# Digital_Port_C_State_LED_Inducator.net
KiCad netlist of a schematic drawn in Altium Designer
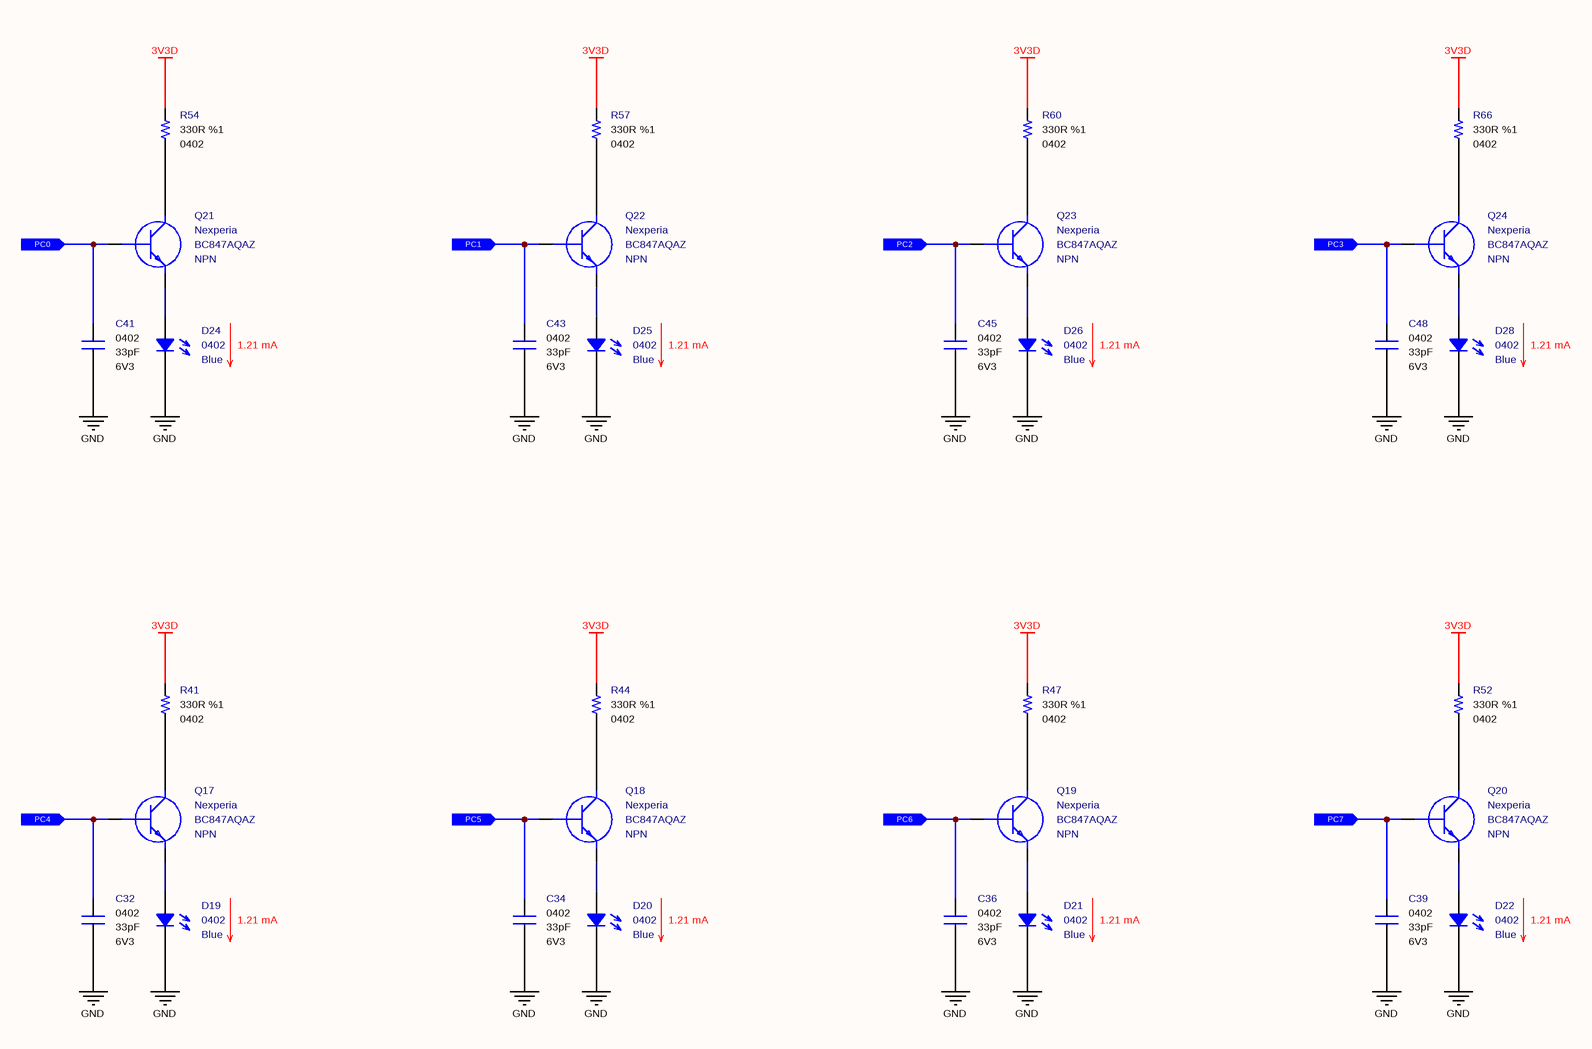
[diagram p0: Digital Port C State LED Inducator.SchDoc]

(export (version "E")
  (design (tool "Eeschema 10.0.6"))
  (components
    (comp (ref "C32")
      (value "33pF")
      (footprint "CAPACITOR_0402")
      (description "Capacitor - 33pF [0402] (Ceramic)")
      (fields
        (field (name "CASE") "0402")
        (field (name "TOLERANCE") "10%")
        (field (name "VOLTAGE") "6V3")
        (field (name "MANUFACTURER PART NUMBER") "C0402C330J9RACAUTO")
      )
      (libsource (lib "Ovoo_Library") (part "Capacitor - 33pF [0402-6V3]"))
    )
    (comp (ref "C34")
      (value "33pF")
      (footprint "CAPACITOR_0402")
      (description "Capacitor - 33pF [0402] (Ceramic)")
      (fields
        (field (name "CASE") "0402")
        (field (name "TOLERANCE") "10%")
        (field (name "VOLTAGE") "6V3")
        (field (name "MANUFACTURER PART NUMBER") "C0402C330J9RACAUTO")
      )
      (libsource (lib "Ovoo_Library") (part "Capacitor - 33pF [0402-6V3]"))
    )
    (comp (ref "C36")
      (value "33pF")
      (footprint "CAPACITOR_0402")
      (description "Capacitor - 33pF [0402] (Ceramic)")
      (fields
        (field (name "CASE") "0402")
        (field (name "TOLERANCE") "10%")
        (field (name "VOLTAGE") "6V3")
        (field (name "MANUFACTURER PART NUMBER") "C0402C330J9RACAUTO")
      )
      (libsource (lib "Ovoo_Library") (part "Capacitor - 33pF [0402-6V3]"))
    )
    (comp (ref "C39")
      (value "33pF")
      (footprint "CAPACITOR_0402")
      (description "Capacitor - 33pF [0402] (Ceramic)")
      (fields
        (field (name "CASE") "0402")
        (field (name "TOLERANCE") "10%")
        (field (name "VOLTAGE") "6V3")
        (field (name "MANUFACTURER PART NUMBER") "C0402C330J9RACAUTO")
      )
      (libsource (lib "Ovoo_Library") (part "Capacitor - 33pF [0402-6V3]"))
    )
    (comp (ref "C41")
      (value "33pF")
      (footprint "CAPACITOR_0402")
      (description "Capacitor - 33pF [0402] (Ceramic)")
      (fields
        (field (name "CASE") "0402")
        (field (name "TOLERANCE") "10%")
        (field (name "VOLTAGE") "6V3")
        (field (name "MANUFACTURER PART NUMBER") "C0402C330J9RACAUTO")
      )
      (libsource (lib "Ovoo_Library") (part "Capacitor - 33pF [0402-6V3]"))
    )
    (comp (ref "C43")
      (value "33pF")
      (footprint "CAPACITOR_0402")
      (description "Capacitor - 33pF [0402] (Ceramic)")
      (fields
        (field (name "CASE") "0402")
        (field (name "TOLERANCE") "10%")
        (field (name "VOLTAGE") "6V3")
        (field (name "MANUFACTURER PART NUMBER") "C0402C330J9RACAUTO")
      )
      (libsource (lib "Ovoo_Library") (part "Capacitor - 33pF [0402-6V3]"))
    )
    (comp (ref "C45")
      (value "33pF")
      (footprint "CAPACITOR_0402")
      (description "Capacitor - 33pF [0402] (Ceramic)")
      (fields
        (field (name "CASE") "0402")
        (field (name "TOLERANCE") "10%")
        (field (name "VOLTAGE") "6V3")
        (field (name "MANUFACTURER PART NUMBER") "C0402C330J9RACAUTO")
      )
      (libsource (lib "Ovoo_Library") (part "Capacitor - 33pF [0402-6V3]"))
    )
    (comp (ref "C48")
      (value "33pF")
      (footprint "CAPACITOR_0402")
      (description "Capacitor - 33pF [0402] (Ceramic)")
      (fields
        (field (name "CASE") "0402")
        (field (name "TOLERANCE") "10%")
        (field (name "VOLTAGE") "6V3")
        (field (name "MANUFACTURER PART NUMBER") "C0402C330J9RACAUTO")
      )
      (libsource (lib "Ovoo_Library") (part "Capacitor - 33pF [0402-6V3]"))
    )
    (comp (ref "D19")
      (value "SMD LED (Blue)")
      (footprint "LED_0402")
      (description "Standard LEDs - SMD PICOLEDTM;BLUE LED; 25M @ 5MA")
      (fields
        (field (name "MANUFACTURER_PART_NUMBER") "SMLP13BC8TT86")
        (field (name "MOUSER_PART_NUMBER") "755-SMLP13BC8TT86")
        (field (name "CASE") "0402")
        (field (name "COLOR") "Blue")
      )
      (libsource (lib "Ovoo_Library") (part "Diode - LED (0402-Blue)"))
    )
    (comp (ref "D20")
      (value "SMD LED (Blue)")
      (footprint "LED_0402")
      (description "Standard LEDs - SMD PICOLEDTM;BLUE LED; 25M @ 5MA")
      (fields
        (field (name "MANUFACTURER_PART_NUMBER") "SMLP13BC8TT86")
        (field (name "MOUSER_PART_NUMBER") "755-SMLP13BC8TT86")
        (field (name "CASE") "0402")
        (field (name "COLOR") "Blue")
      )
      (libsource (lib "Ovoo_Library") (part "Diode - LED (0402-Blue)"))
    )
    (comp (ref "D21")
      (value "SMD LED (Blue)")
      (footprint "LED_0402")
      (description "Standard LEDs - SMD PICOLEDTM;BLUE LED; 25M @ 5MA")
      (fields
        (field (name "MANUFACTURER_PART_NUMBER") "SMLP13BC8TT86")
        (field (name "MOUSER_PART_NUMBER") "755-SMLP13BC8TT86")
        (field (name "CASE") "0402")
        (field (name "COLOR") "Blue")
      )
      (libsource (lib "Ovoo_Library") (part "Diode - LED (0402-Blue)"))
    )
    (comp (ref "D22")
      (value "SMD LED (Blue)")
      (footprint "LED_0402")
      (description "Standard LEDs - SMD PICOLEDTM;BLUE LED; 25M @ 5MA")
      (fields
        (field (name "MANUFACTURER_PART_NUMBER") "SMLP13BC8TT86")
        (field (name "MOUSER_PART_NUMBER") "755-SMLP13BC8TT86")
        (field (name "CASE") "0402")
        (field (name "COLOR") "Blue")
      )
      (libsource (lib "Ovoo_Library") (part "Diode - LED (0402-Blue)"))
    )
    (comp (ref "D24")
      (value "SMD LED (Blue)")
      (footprint "LED_0402")
      (description "Standard LEDs - SMD PICOLEDTM;BLUE LED; 25M @ 5MA")
      (fields
        (field (name "MANUFACTURER_PART_NUMBER") "SMLP13BC8TT86")
        (field (name "MOUSER_PART_NUMBER") "755-SMLP13BC8TT86")
        (field (name "CASE") "0402")
        (field (name "COLOR") "Blue")
      )
      (libsource (lib "Ovoo_Library") (part "Diode - LED (0402-Blue)"))
    )
    (comp (ref "D25")
      (value "SMD LED (Blue)")
      (footprint "LED_0402")
      (description "Standard LEDs - SMD PICOLEDTM;BLUE LED; 25M @ 5MA")
      (fields
        (field (name "MANUFACTURER_PART_NUMBER") "SMLP13BC8TT86")
        (field (name "MOUSER_PART_NUMBER") "755-SMLP13BC8TT86")
        (field (name "CASE") "0402")
        (field (name "COLOR") "Blue")
      )
      (libsource (lib "Ovoo_Library") (part "Diode - LED (0402-Blue)"))
    )
    (comp (ref "D26")
      (value "SMD LED (Blue)")
      (footprint "LED_0402")
      (description "Standard LEDs - SMD PICOLEDTM;BLUE LED; 25M @ 5MA")
      (fields
        (field (name "MANUFACTURER_PART_NUMBER") "SMLP13BC8TT86")
        (field (name "MOUSER_PART_NUMBER") "755-SMLP13BC8TT86")
        (field (name "CASE") "0402")
        (field (name "COLOR") "Blue")
      )
      (libsource (lib "Ovoo_Library") (part "Diode - LED (0402-Blue)"))
    )
    (comp (ref "D28")
      (value "SMD LED (Blue)")
      (footprint "LED_0402")
      (description "Standard LEDs - SMD PICOLEDTM;BLUE LED; 25M @ 5MA")
      (fields
        (field (name "MANUFACTURER_PART_NUMBER") "SMLP13BC8TT86")
        (field (name "MOUSER_PART_NUMBER") "755-SMLP13BC8TT86")
        (field (name "CASE") "0402")
        (field (name "COLOR") "Blue")
      )
      (libsource (lib "Ovoo_Library") (part "Diode - LED (0402-Blue)"))
    )
    (comp (ref "Q17")
      (value "Bipolar NPN Transistors")
      (footprint "SOT1215")
      (description "Bipolar Transistors - BJT BC847AQA/DFN1010D-3/REEL 7\" Q2")
      (fields
        (field (name "MOUSER_PART_NUMBER") "771-BC847AQAZ")
        (field (name "MANUFACTURER_NAME") "Nexperia")
        (field (name "MANUFACTURER_PART_NUMBER") "BC847AQAZ")
        (field (name "POLARITY") "NPN")
      )
      (libsource (lib "Ovoo_Library") (part "Transistor - BC847"))
    )
    (comp (ref "Q18")
      (value "Bipolar NPN Transistors")
      (footprint "SOT1215")
      (description "Bipolar Transistors - BJT BC847AQA/DFN1010D-3/REEL 7\" Q2")
      (fields
        (field (name "MOUSER_PART_NUMBER") "771-BC847AQAZ")
        (field (name "MANUFACTURER_NAME") "Nexperia")
        (field (name "MANUFACTURER_PART_NUMBER") "BC847AQAZ")
        (field (name "POLARITY") "NPN")
      )
      (libsource (lib "Ovoo_Library") (part "Transistor - BC847"))
    )
    (comp (ref "Q19")
      (value "Bipolar NPN Transistors")
      (footprint "SOT1215")
      (description "Bipolar Transistors - BJT BC847AQA/DFN1010D-3/REEL 7\" Q2")
      (fields
        (field (name "MOUSER_PART_NUMBER") "771-BC847AQAZ")
        (field (name "MANUFACTURER_NAME") "Nexperia")
        (field (name "MANUFACTURER_PART_NUMBER") "BC847AQAZ")
        (field (name "POLARITY") "NPN")
      )
      (libsource (lib "Ovoo_Library") (part "Transistor - BC847"))
    )
    (comp (ref "Q20")
      (value "Bipolar NPN Transistors")
      (footprint "SOT1215")
      (description "Bipolar Transistors - BJT BC847AQA/DFN1010D-3/REEL 7\" Q2")
      (fields
        (field (name "MOUSER_PART_NUMBER") "771-BC847AQAZ")
        (field (name "MANUFACTURER_NAME") "Nexperia")
        (field (name "MANUFACTURER_PART_NUMBER") "BC847AQAZ")
        (field (name "POLARITY") "NPN")
      )
      (libsource (lib "Ovoo_Library") (part "Transistor - BC847"))
    )
    (comp (ref "Q21")
      (value "Bipolar NPN Transistors")
      (footprint "SOT1215")
      (description "Bipolar Transistors - BJT BC847AQA/DFN1010D-3/REEL 7\" Q2")
      (fields
        (field (name "MOUSER_PART_NUMBER") "771-BC847AQAZ")
        (field (name "MANUFACTURER_NAME") "Nexperia")
        (field (name "MANUFACTURER_PART_NUMBER") "BC847AQAZ")
        (field (name "POLARITY") "NPN")
      )
      (libsource (lib "Ovoo_Library") (part "Transistor - BC847"))
    )
    (comp (ref "Q22")
      (value "Bipolar NPN Transistors")
      (footprint "SOT1215")
      (description "Bipolar Transistors - BJT BC847AQA/DFN1010D-3/REEL 7\" Q2")
      (fields
        (field (name "MOUSER_PART_NUMBER") "771-BC847AQAZ")
        (field (name "MANUFACTURER_NAME") "Nexperia")
        (field (name "MANUFACTURER_PART_NUMBER") "BC847AQAZ")
        (field (name "POLARITY") "NPN")
      )
      (libsource (lib "Ovoo_Library") (part "Transistor - BC847"))
    )
    (comp (ref "Q23")
      (value "Bipolar NPN Transistors")
      (footprint "SOT1215")
      (description "Bipolar Transistors - BJT BC847AQA/DFN1010D-3/REEL 7\" Q2")
      (fields
        (field (name "MOUSER_PART_NUMBER") "771-BC847AQAZ")
        (field (name "MANUFACTURER_NAME") "Nexperia")
        (field (name "MANUFACTURER_PART_NUMBER") "BC847AQAZ")
        (field (name "POLARITY") "NPN")
      )
      (libsource (lib "Ovoo_Library") (part "Transistor - BC847"))
    )
    (comp (ref "Q24")
      (value "Bipolar NPN Transistors")
      (footprint "SOT1215")
      (description "Bipolar Transistors - BJT BC847AQA/DFN1010D-3/REEL 7\" Q2")
      (fields
        (field (name "MOUSER_PART_NUMBER") "771-BC847AQAZ")
        (field (name "MANUFACTURER_NAME") "Nexperia")
        (field (name "MANUFACTURER_PART_NUMBER") "BC847AQAZ")
        (field (name "POLARITY") "NPN")
      )
      (libsource (lib "Ovoo_Library") (part "Transistor - BC847"))
    )
    (comp (ref "R41")
      (value "330R")
      (footprint "RESISTOR_0402")
      (description "Thick Film Resistors - SMD 1/16 W 330 Ohm 1%")
      (fields
        (field (name "TOLERANCE") "%1")
        (field (name "CASE") "0402")
        (field (name "MANUFACTURER PART NUMBER") "CRCW0402330RFKED")
        (field (name "MOUSER PART NUMBER") "71-CRCW0402-330-E3")
      )
      (libsource (lib "Ovoo_Library") (part "Resistor - 330R"))
    )
    (comp (ref "R44")
      (value "330R")
      (footprint "RESISTOR_0402")
      (description "Thick Film Resistors - SMD 1/16 W 330 Ohm 1%")
      (fields
        (field (name "TOLERANCE") "%1")
        (field (name "CASE") "0402")
        (field (name "MANUFACTURER PART NUMBER") "CRCW0402330RFKED")
        (field (name "MOUSER PART NUMBER") "71-CRCW0402-330-E3")
      )
      (libsource (lib "Ovoo_Library") (part "Resistor - 330R"))
    )
    (comp (ref "R47")
      (value "330R")
      (footprint "RESISTOR_0402")
      (description "Thick Film Resistors - SMD 1/16 W 330 Ohm 1%")
      (fields
        (field (name "TOLERANCE") "%1")
        (field (name "CASE") "0402")
        (field (name "MANUFACTURER PART NUMBER") "CRCW0402330RFKED")
        (field (name "MOUSER PART NUMBER") "71-CRCW0402-330-E3")
      )
      (libsource (lib "Ovoo_Library") (part "Resistor - 330R"))
    )
    (comp (ref "R52")
      (value "330R")
      (footprint "RESISTOR_0402")
      (description "Thick Film Resistors - SMD 1/16 W 330 Ohm 1%")
      (fields
        (field (name "TOLERANCE") "%1")
        (field (name "CASE") "0402")
        (field (name "MANUFACTURER PART NUMBER") "CRCW0402330RFKED")
        (field (name "MOUSER PART NUMBER") "71-CRCW0402-330-E3")
      )
      (libsource (lib "Ovoo_Library") (part "Resistor - 330R"))
    )
    (comp (ref "R54")
      (value "330R")
      (footprint "RESISTOR_0402")
      (description "Thick Film Resistors - SMD 1/16 W 330 Ohm 1%")
      (fields
        (field (name "TOLERANCE") "%1")
        (field (name "CASE") "0402")
        (field (name "MANUFACTURER PART NUMBER") "CRCW0402330RFKED")
        (field (name "MOUSER PART NUMBER") "71-CRCW0402-330-E3")
      )
      (libsource (lib "Ovoo_Library") (part "Resistor - 330R"))
    )
    (comp (ref "R57")
      (value "330R")
      (footprint "RESISTOR_0402")
      (description "Thick Film Resistors - SMD 1/16 W 330 Ohm 1%")
      (fields
        (field (name "TOLERANCE") "%1")
        (field (name "CASE") "0402")
        (field (name "MANUFACTURER PART NUMBER") "CRCW0402330RFKED")
        (field (name "MOUSER PART NUMBER") "71-CRCW0402-330-E3")
      )
      (libsource (lib "Ovoo_Library") (part "Resistor - 330R"))
    )
    (comp (ref "R60")
      (value "330R")
      (footprint "RESISTOR_0402")
      (description "Thick Film Resistors - SMD 1/16 W 330 Ohm 1%")
      (fields
        (field (name "TOLERANCE") "%1")
        (field (name "CASE") "0402")
        (field (name "MANUFACTURER PART NUMBER") "CRCW0402330RFKED")
        (field (name "MOUSER PART NUMBER") "71-CRCW0402-330-E3")
      )
      (libsource (lib "Ovoo_Library") (part "Resistor - 330R"))
    )
    (comp (ref "R66")
      (value "330R")
      (footprint "RESISTOR_0402")
      (description "Thick Film Resistors - SMD 1/16 W 330 Ohm 1%")
      (fields
        (field (name "TOLERANCE") "%1")
        (field (name "CASE") "0402")
        (field (name "MANUFACTURER PART NUMBER") "CRCW0402330RFKED")
        (field (name "MOUSER PART NUMBER") "71-CRCW0402-330-E3")
      )
      (libsource (lib "Ovoo_Library") (part "Resistor - 330R"))
    )
  )
  (nets
    (net (code "1") (name "/PC0") (class "Default")
      (node (ref "C41") (pin "1") (pinfunction "1_1") (pintype "passive"))
      (node (ref "Q21") (pin "1") (pinfunction "B_1") (pintype "passive"))
    )
    (net (code "2") (name "/PC1") (class "Default")
      (node (ref "C43") (pin "1") (pinfunction "1_1") (pintype "passive"))
      (node (ref "Q22") (pin "1") (pinfunction "B_1") (pintype "passive"))
    )
    (net (code "3") (name "/PC2") (class "Default")
      (node (ref "C45") (pin "1") (pinfunction "1_1") (pintype "passive"))
      (node (ref "Q23") (pin "1") (pinfunction "B_1") (pintype "passive"))
    )
    (net (code "4") (name "/PC3") (class "Default")
      (node (ref "C48") (pin "1") (pinfunction "1_1") (pintype "passive"))
      (node (ref "Q24") (pin "1") (pinfunction "B_1") (pintype "passive"))
    )
    (net (code "5") (name "/PC4") (class "Default")
      (node (ref "C32") (pin "1") (pinfunction "1_1") (pintype "passive"))
      (node (ref "Q17") (pin "1") (pinfunction "B_1") (pintype "passive"))
    )
    (net (code "6") (name "/PC5") (class "Default")
      (node (ref "C34") (pin "1") (pinfunction "1_1") (pintype "passive"))
      (node (ref "Q18") (pin "1") (pinfunction "B_1") (pintype "passive"))
    )
    (net (code "7") (name "/PC6") (class "Default")
      (node (ref "C36") (pin "1") (pinfunction "1_1") (pintype "passive"))
      (node (ref "Q19") (pin "1") (pinfunction "B_1") (pintype "passive"))
    )
    (net (code "8") (name "/PC7") (class "Default")
      (node (ref "C39") (pin "1") (pinfunction "1_1") (pintype "passive"))
      (node (ref "Q20") (pin "1") (pinfunction "B_1") (pintype "passive"))
    )
    (net (code "9") (name "3V3D") (class "Default")
      (node (ref "R41") (pin "2") (pinfunction "2_2") (pintype "passive"))
      (node (ref "R44") (pin "2") (pinfunction "2_2") (pintype "passive"))
      (node (ref "R47") (pin "2") (pinfunction "2_2") (pintype "passive"))
      (node (ref "R52") (pin "2") (pinfunction "2_2") (pintype "passive"))
      (node (ref "R54") (pin "2") (pinfunction "2_2") (pintype "passive"))
      (node (ref "R57") (pin "2") (pinfunction "2_2") (pintype "passive"))
      (node (ref "R60") (pin "2") (pinfunction "2_2") (pintype "passive"))
      (node (ref "R66") (pin "2") (pinfunction "2_2") (pintype "passive"))
    )
    (net (code "10") (name "GND") (class "Default")
      (node (ref "C32") (pin "2") (pinfunction "2_2") (pintype "passive"))
      (node (ref "C34") (pin "2") (pinfunction "2_2") (pintype "passive"))
      (node (ref "C36") (pin "2") (pinfunction "2_2") (pintype "passive"))
      (node (ref "C39") (pin "2") (pinfunction "2_2") (pintype "passive"))
      (node (ref "C41") (pin "2") (pinfunction "2_2") (pintype "passive"))
      (node (ref "C43") (pin "2") (pinfunction "2_2") (pintype "passive"))
      (node (ref "C45") (pin "2") (pinfunction "2_2") (pintype "passive"))
      (node (ref "C48") (pin "2") (pinfunction "2_2") (pintype "passive"))
      (node (ref "D19") (pin "1") (pinfunction "1_1") (pintype "passive"))
      (node (ref "D20") (pin "1") (pinfunction "1_1") (pintype "passive"))
      (node (ref "D21") (pin "1") (pinfunction "1_1") (pintype "passive"))
      (node (ref "D22") (pin "1") (pinfunction "1_1") (pintype "passive"))
      (node (ref "D24") (pin "1") (pinfunction "1_1") (pintype "passive"))
      (node (ref "D25") (pin "1") (pinfunction "1_1") (pintype "passive"))
      (node (ref "D26") (pin "1") (pinfunction "1_1") (pintype "passive"))
      (node (ref "D28") (pin "1") (pinfunction "1_1") (pintype "passive"))
    )
    (net (code "11") (name "Net-(Q17-C)") (class "Default")
      (node (ref "Q17") (pin "3") (pinfunction "C_3") (pintype "passive"))
      (node (ref "R41") (pin "1") (pinfunction "1_1") (pintype "passive"))
    )
    (net (code "12") (name "Net-(Q17-E)") (class "Default")
      (node (ref "D19") (pin "2") (pinfunction "2_2") (pintype "passive"))
      (node (ref "Q17") (pin "2") (pinfunction "E_2") (pintype "passive"))
    )
    (net (code "13") (name "Net-(Q18-C)") (class "Default")
      (node (ref "Q18") (pin "3") (pinfunction "C_3") (pintype "passive"))
      (node (ref "R44") (pin "1") (pinfunction "1_1") (pintype "passive"))
    )
    (net (code "14") (name "Net-(Q18-E)") (class "Default")
      (node (ref "D20") (pin "2") (pinfunction "2_2") (pintype "passive"))
      (node (ref "Q18") (pin "2") (pinfunction "E_2") (pintype "passive"))
    )
    (net (code "15") (name "Net-(Q19-C)") (class "Default")
      (node (ref "Q19") (pin "3") (pinfunction "C_3") (pintype "passive"))
      (node (ref "R47") (pin "1") (pinfunction "1_1") (pintype "passive"))
    )
    (net (code "16") (name "Net-(Q19-E)") (class "Default")
      (node (ref "D21") (pin "2") (pinfunction "2_2") (pintype "passive"))
      (node (ref "Q19") (pin "2") (pinfunction "E_2") (pintype "passive"))
    )
    (net (code "17") (name "Net-(Q20-C)") (class "Default")
      (node (ref "Q20") (pin "3") (pinfunction "C_3") (pintype "passive"))
      (node (ref "R52") (pin "1") (pinfunction "1_1") (pintype "passive"))
    )
    (net (code "18") (name "Net-(Q20-E)") (class "Default")
      (node (ref "D22") (pin "2") (pinfunction "2_2") (pintype "passive"))
      (node (ref "Q20") (pin "2") (pinfunction "E_2") (pintype "passive"))
    )
    (net (code "19") (name "Net-(Q21-C)") (class "Default")
      (node (ref "Q21") (pin "3") (pinfunction "C_3") (pintype "passive"))
      (node (ref "R54") (pin "1") (pinfunction "1_1") (pintype "passive"))
    )
    (net (code "20") (name "Net-(Q21-E)") (class "Default")
      (node (ref "D24") (pin "2") (pinfunction "2_2") (pintype "passive"))
      (node (ref "Q21") (pin "2") (pinfunction "E_2") (pintype "passive"))
    )
    (net (code "21") (name "Net-(Q22-C)") (class "Default")
      (node (ref "Q22") (pin "3") (pinfunction "C_3") (pintype "passive"))
      (node (ref "R57") (pin "1") (pinfunction "1_1") (pintype "passive"))
    )
    (net (code "22") (name "Net-(Q22-E)") (class "Default")
      (node (ref "D25") (pin "2") (pinfunction "2_2") (pintype "passive"))
      (node (ref "Q22") (pin "2") (pinfunction "E_2") (pintype "passive"))
    )
    (net (code "23") (name "Net-(Q23-C)") (class "Default")
      (node (ref "Q23") (pin "3") (pinfunction "C_3") (pintype "passive"))
      (node (ref "R60") (pin "1") (pinfunction "1_1") (pintype "passive"))
    )
    (net (code "24") (name "Net-(Q23-E)") (class "Default")
      (node (ref "D26") (pin "2") (pinfunction "2_2") (pintype "passive"))
      (node (ref "Q23") (pin "2") (pinfunction "E_2") (pintype "passive"))
    )
    (net (code "25") (name "Net-(Q24-C)") (class "Default")
      (node (ref "Q24") (pin "3") (pinfunction "C_3") (pintype "passive"))
      (node (ref "R66") (pin "1") (pinfunction "1_1") (pintype "passive"))
    )
    (net (code "26") (name "Net-(Q24-E)") (class "Default")
      (node (ref "D28") (pin "2") (pinfunction "2_2") (pintype "passive"))
      (node (ref "Q24") (pin "2") (pinfunction "E_2") (pintype "passive"))
    )
  )
)
